# Board_Jam_v3.net
KiCad netlist of a schematic drawn in EAGLE
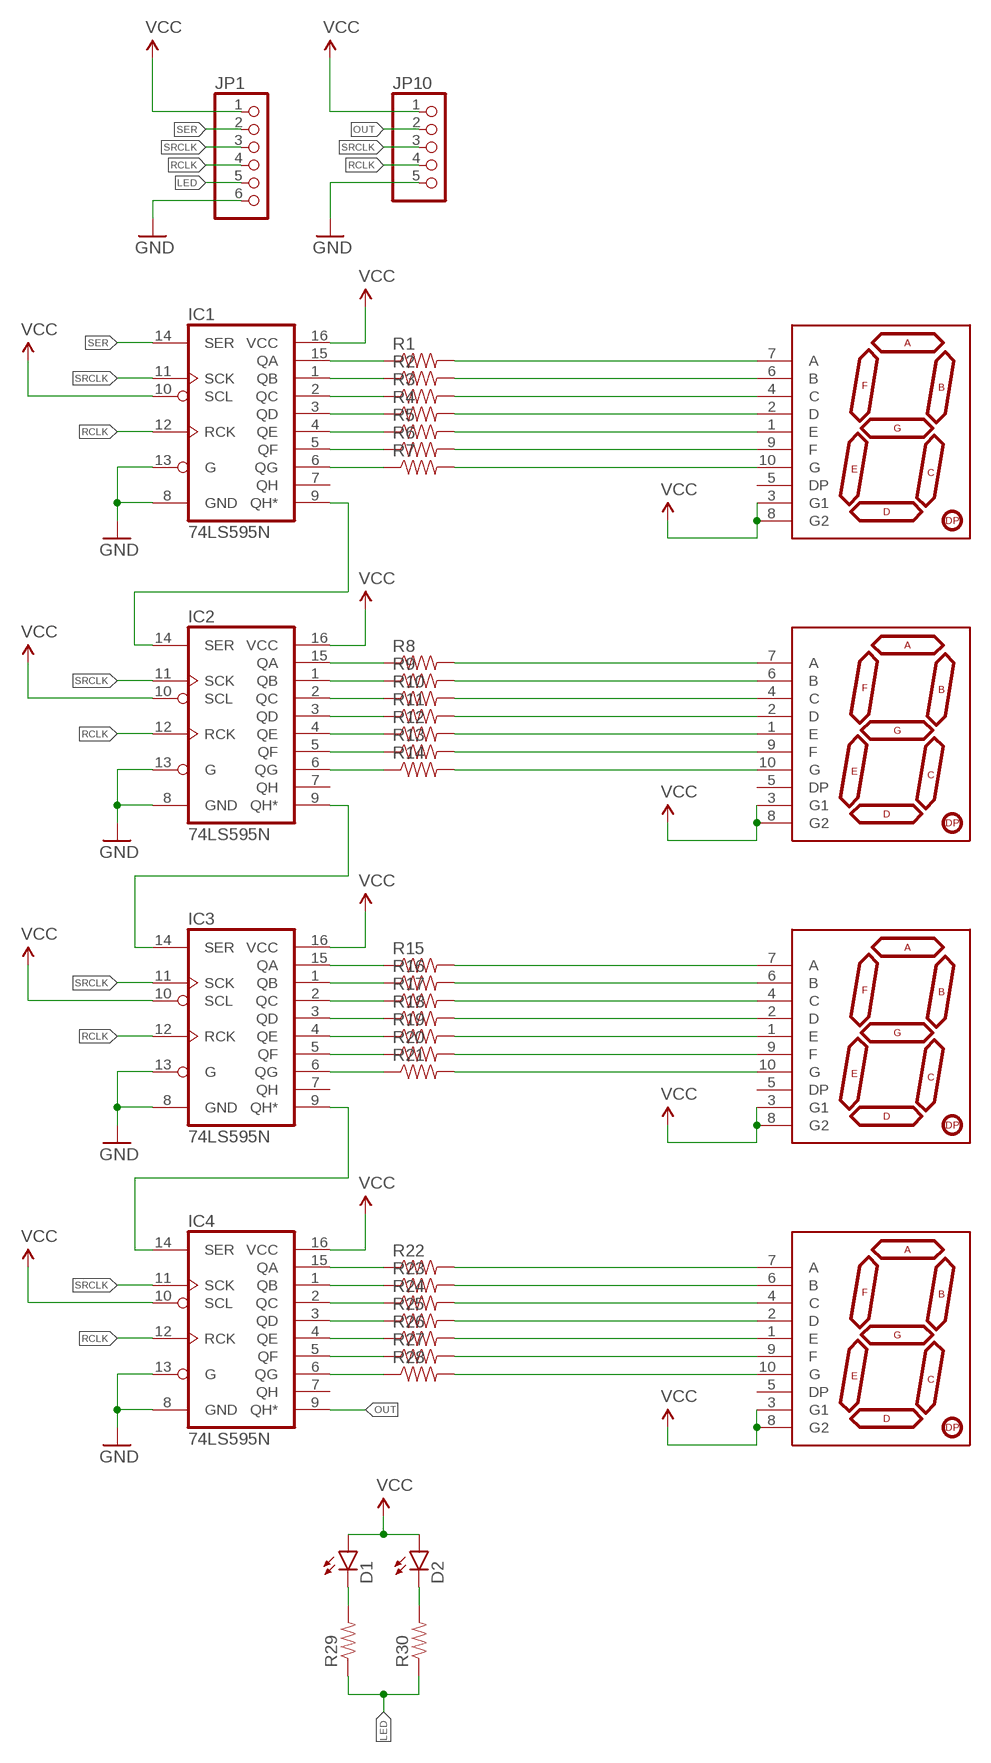
[diagram p0: schematic, sheet 1]

(export (version "E")
  (design (tool "Eeschema 10.0.6"))
  (components
    (comp (ref "D1")
      (value "LED3MM")
      (footprint "eagle-import:LED3MM")
      (libsource (lib "eagle-import") (part "LED3MM"))
    )
    (comp (ref "D2")
      (value "LED3MM")
      (footprint "eagle-import:LED3MM")
      (libsource (lib "eagle-import") (part "LED3MM"))
    )
    (comp (ref "IC1")
      (value "74LS595N")
      (footprint "eagle-import:DIL16")
      (libsource (lib "eagle-import") (part "74595NLS"))
    )
    (comp (ref "IC2")
      (value "74LS595N")
      (footprint "eagle-import:DIL16")
      (libsource (lib "eagle-import") (part "74595NLS"))
    )
    (comp (ref "IC3")
      (value "74LS595N")
      (footprint "eagle-import:DIL16")
      (libsource (lib "eagle-import") (part "74595NLS"))
    )
    (comp (ref "IC4")
      (value "74LS595N")
      (footprint "eagle-import:DIL16")
      (libsource (lib "eagle-import") (part "74595NLS"))
    )
    (comp (ref "JP1")
      (value "PINHD-1X6")
      (footprint "eagle-import:1X06")
      (libsource (lib "eagle-import") (part "PINHD-1X6"))
    )
    (comp (ref "JP10")
      (value "PINHD-1X5")
      (footprint "eagle-import:1X05")
      (libsource (lib "eagle-import") (part "PINHD-1X5"))
    )
    (comp (ref "R1")
      (value "RESISTORPTH-1/4W")
      (footprint "eagle-import:AXIAL-0.4")
      (libsource (lib "eagle-import") (part "RESISTORPTH-1/4W"))
    )
    (comp (ref "R2")
      (value "RESISTORPTH-1/4W")
      (footprint "eagle-import:AXIAL-0.4")
      (libsource (lib "eagle-import") (part "RESISTORPTH-1/4W"))
    )
    (comp (ref "R3")
      (value "RESISTORPTH-1/4W")
      (footprint "eagle-import:AXIAL-0.4")
      (libsource (lib "eagle-import") (part "RESISTORPTH-1/4W"))
    )
    (comp (ref "R4")
      (value "RESISTORPTH-1/4W")
      (footprint "eagle-import:AXIAL-0.4")
      (libsource (lib "eagle-import") (part "RESISTORPTH-1/4W"))
    )
    (comp (ref "R5")
      (value "RESISTORPTH-1/4W")
      (footprint "eagle-import:AXIAL-0.4")
      (libsource (lib "eagle-import") (part "RESISTORPTH-1/4W"))
    )
    (comp (ref "R6")
      (value "RESISTORPTH-1/4W")
      (footprint "eagle-import:AXIAL-0.4")
      (libsource (lib "eagle-import") (part "RESISTORPTH-1/4W"))
    )
    (comp (ref "R7")
      (value "RESISTORPTH-1/4W")
      (footprint "eagle-import:AXIAL-0.4")
      (libsource (lib "eagle-import") (part "RESISTORPTH-1/4W"))
    )
    (comp (ref "R8")
      (value "RESISTORPTH-1/4W")
      (footprint "eagle-import:AXIAL-0.4")
      (libsource (lib "eagle-import") (part "RESISTORPTH-1/4W"))
    )
    (comp (ref "R9")
      (value "RESISTORPTH-1/4W")
      (footprint "eagle-import:AXIAL-0.4")
      (libsource (lib "eagle-import") (part "RESISTORPTH-1/4W"))
    )
    (comp (ref "R10")
      (value "RESISTORPTH-1/4W")
      (footprint "eagle-import:AXIAL-0.4")
      (libsource (lib "eagle-import") (part "RESISTORPTH-1/4W"))
    )
    (comp (ref "R11")
      (value "RESISTORPTH-1/4W")
      (footprint "eagle-import:AXIAL-0.4")
      (libsource (lib "eagle-import") (part "RESISTORPTH-1/4W"))
    )
    (comp (ref "R12")
      (value "RESISTORPTH-1/4W")
      (footprint "eagle-import:AXIAL-0.4")
      (libsource (lib "eagle-import") (part "RESISTORPTH-1/4W"))
    )
    (comp (ref "R13")
      (value "RESISTORPTH-1/4W")
      (footprint "eagle-import:AXIAL-0.4")
      (libsource (lib "eagle-import") (part "RESISTORPTH-1/4W"))
    )
    (comp (ref "R14")
      (value "RESISTORPTH-1/4W")
      (footprint "eagle-import:AXIAL-0.4")
      (libsource (lib "eagle-import") (part "RESISTORPTH-1/4W"))
    )
    (comp (ref "R15")
      (value "RESISTORPTH-1/4W")
      (footprint "eagle-import:AXIAL-0.4")
      (libsource (lib "eagle-import") (part "RESISTORPTH-1/4W"))
    )
    (comp (ref "R16")
      (value "RESISTORPTH-1/4W")
      (footprint "eagle-import:AXIAL-0.4")
      (libsource (lib "eagle-import") (part "RESISTORPTH-1/4W"))
    )
    (comp (ref "R17")
      (value "RESISTORPTH-1/4W")
      (footprint "eagle-import:AXIAL-0.4")
      (libsource (lib "eagle-import") (part "RESISTORPTH-1/4W"))
    )
    (comp (ref "R18")
      (value "RESISTORPTH-1/4W")
      (footprint "eagle-import:AXIAL-0.4")
      (libsource (lib "eagle-import") (part "RESISTORPTH-1/4W"))
    )
    (comp (ref "R19")
      (value "RESISTORPTH-1/4W")
      (footprint "eagle-import:AXIAL-0.4")
      (libsource (lib "eagle-import") (part "RESISTORPTH-1/4W"))
    )
    (comp (ref "R20")
      (value "RESISTORPTH-1/4W")
      (footprint "eagle-import:AXIAL-0.4")
      (libsource (lib "eagle-import") (part "RESISTORPTH-1/4W"))
    )
    (comp (ref "R21")
      (value "RESISTORPTH-1/4W")
      (footprint "eagle-import:AXIAL-0.4")
      (libsource (lib "eagle-import") (part "RESISTORPTH-1/4W"))
    )
    (comp (ref "R22")
      (value "RESISTORPTH-1/4W")
      (footprint "eagle-import:AXIAL-0.4")
      (libsource (lib "eagle-import") (part "RESISTORPTH-1/4W"))
    )
    (comp (ref "R23")
      (value "RESISTORPTH-1/4W")
      (footprint "eagle-import:AXIAL-0.4")
      (libsource (lib "eagle-import") (part "RESISTORPTH-1/4W"))
    )
    (comp (ref "R24")
      (value "RESISTORPTH-1/4W")
      (footprint "eagle-import:AXIAL-0.4")
      (libsource (lib "eagle-import") (part "RESISTORPTH-1/4W"))
    )
    (comp (ref "R25")
      (value "RESISTORPTH-1/4W")
      (footprint "eagle-import:AXIAL-0.4")
      (libsource (lib "eagle-import") (part "RESISTORPTH-1/4W"))
    )
    (comp (ref "R26")
      (value "RESISTORPTH-1/4W")
      (footprint "eagle-import:AXIAL-0.4")
      (libsource (lib "eagle-import") (part "RESISTORPTH-1/4W"))
    )
    (comp (ref "R27")
      (value "RESISTORPTH-1/4W")
      (footprint "eagle-import:AXIAL-0.4")
      (libsource (lib "eagle-import") (part "RESISTORPTH-1/4W"))
    )
    (comp (ref "R28")
      (value "RESISTORPTH-1/4W")
      (footprint "eagle-import:AXIAL-0.4")
      (libsource (lib "eagle-import") (part "RESISTORPTH-1/4W"))
    )
    (comp (ref "R29")
      (value "RESISTORPTH-1/4W")
      (footprint "eagle-import:AXIAL-0.4")
      (libsource (lib "eagle-import") (part "RESISTORPTH-1/4W"))
    )
    (comp (ref "R30")
      (value "RESISTORPTH-1/4W")
      (footprint "eagle-import:AXIAL-0.4")
      (libsource (lib "eagle-import") (part "RESISTORPTH-1/4W"))
    )
    (comp (ref "U$1")
      (value "7-SEGMENT-DISPLAY-1\"-REDEZ")
      (footprint "eagle-import:7-SEGMENT-1_PTH-EZ")
      (libsource (lib "eagle-import") (part "7-SEGMENT-DISPLAY-1{dblquote}-REDEZ"))
    )
    (comp (ref "U$2")
      (value "7-SEGMENT-DISPLAY-1\"-REDEZ")
      (footprint "eagle-import:7-SEGMENT-1_PTH-EZ")
      (libsource (lib "eagle-import") (part "7-SEGMENT-DISPLAY-1{dblquote}-REDEZ"))
    )
    (comp (ref "U$3")
      (value "7-SEGMENT-DISPLAY-1\"-REDEZ")
      (footprint "eagle-import:7-SEGMENT-1_PTH-EZ")
      (libsource (lib "eagle-import") (part "7-SEGMENT-DISPLAY-1{dblquote}-REDEZ"))
    )
    (comp (ref "U$4")
      (value "7-SEGMENT-DISPLAY-1\"-REDEZ")
      (footprint "eagle-import:7-SEGMENT-1_PTH-EZ")
      (libsource (lib "eagle-import") (part "7-SEGMENT-DISPLAY-1{dblquote}-REDEZ"))
    )
  )
  (nets
    (net (code "1") (name "GND") (class "Default")
      (node (ref "IC1") (pin "13") (pinfunction "G_13") (pintype "input"))
      (node (ref "IC1") (pin "8") (pinfunction "GND_8") (pintype "power_in"))
      (node (ref "IC2") (pin "13") (pinfunction "G_13") (pintype "input"))
      (node (ref "IC2") (pin "8") (pinfunction "GND_8") (pintype "power_in"))
      (node (ref "IC3") (pin "13") (pinfunction "G_13") (pintype "input"))
      (node (ref "IC3") (pin "8") (pinfunction "GND_8") (pintype "power_in"))
      (node (ref "IC4") (pin "13") (pinfunction "G_13") (pintype "input"))
      (node (ref "IC4") (pin "8") (pinfunction "GND_8") (pintype "power_in"))
      (node (ref "JP1") (pin "6") (pinfunction "6_6") (pintype "passive"))
      (node (ref "JP10") (pin "5") (pinfunction "5_5") (pintype "passive"))
    )
    (net (code "2") (name "LED") (class "Default")
      (node (ref "JP1") (pin "5") (pinfunction "5_5") (pintype "passive"))
      (node (ref "R29") (pin "P$1") (pinfunction "1_P$1") (pintype "passive"))
      (node (ref "R30") (pin "P$1") (pinfunction "1_P$1") (pintype "passive"))
    )
    (net (code "3") (name "Net-(D1-C)") (class "Default")
      (node (ref "D1") (pin "K") (pinfunction "C_K") (pintype "passive"))
      (node (ref "R29") (pin "P$2") (pinfunction "2_P$2") (pintype "passive"))
    )
    (net (code "4") (name "Net-(D2-C)") (class "Default")
      (node (ref "D2") (pin "K") (pinfunction "C_K") (pintype "passive"))
      (node (ref "R30") (pin "P$2") (pinfunction "2_P$2") (pintype "passive"))
    )
    (net (code "5") (name "Net-(IC1-QA)") (class "Default")
      (node (ref "IC1") (pin "15") (pinfunction "QA_15") (pintype "tri_state"))
      (node (ref "R1") (pin "P$1") (pinfunction "1_P$1") (pintype "passive"))
    )
    (net (code "6") (name "Net-(IC1-QB)") (class "Default")
      (node (ref "IC1") (pin "1") (pinfunction "QB_1") (pintype "tri_state"))
      (node (ref "R2") (pin "P$1") (pinfunction "1_P$1") (pintype "passive"))
    )
    (net (code "7") (name "Net-(IC1-QC)") (class "Default")
      (node (ref "IC1") (pin "2") (pinfunction "QC_2") (pintype "tri_state"))
      (node (ref "R3") (pin "P$1") (pinfunction "1_P$1") (pintype "passive"))
    )
    (net (code "8") (name "Net-(IC1-QD)") (class "Default")
      (node (ref "IC1") (pin "3") (pinfunction "QD_3") (pintype "tri_state"))
      (node (ref "R4") (pin "P$1") (pinfunction "1_P$1") (pintype "passive"))
    )
    (net (code "9") (name "Net-(IC1-QE)") (class "Default")
      (node (ref "IC1") (pin "4") (pinfunction "QE_4") (pintype "tri_state"))
      (node (ref "R5") (pin "P$1") (pinfunction "1_P$1") (pintype "passive"))
    )
    (net (code "10") (name "Net-(IC1-QF)") (class "Default")
      (node (ref "IC1") (pin "5") (pinfunction "QF_5") (pintype "tri_state"))
      (node (ref "R6") (pin "P$1") (pinfunction "1_P$1") (pintype "passive"))
    )
    (net (code "11") (name "Net-(IC1-QG)") (class "Default")
      (node (ref "IC1") (pin "6") (pinfunction "QG_6") (pintype "tri_state"))
      (node (ref "R7") (pin "P$1") (pinfunction "1_P$1") (pintype "passive"))
    )
    (net (code "12") (name "Net-(IC1-QH*)") (class "Default")
      (node (ref "IC1") (pin "9") (pinfunction "QH*_9") (pintype "tri_state"))
      (node (ref "IC2") (pin "14") (pinfunction "SER_14") (pintype "input"))
    )
    (net (code "13") (name "Net-(IC2-QA)") (class "Default")
      (node (ref "IC2") (pin "15") (pinfunction "QA_15") (pintype "tri_state"))
      (node (ref "R8") (pin "P$1") (pinfunction "1_P$1") (pintype "passive"))
    )
    (net (code "14") (name "Net-(IC2-QB)") (class "Default")
      (node (ref "IC2") (pin "1") (pinfunction "QB_1") (pintype "tri_state"))
      (node (ref "R9") (pin "P$1") (pinfunction "1_P$1") (pintype "passive"))
    )
    (net (code "15") (name "Net-(IC2-QC)") (class "Default")
      (node (ref "IC2") (pin "2") (pinfunction "QC_2") (pintype "tri_state"))
      (node (ref "R10") (pin "P$1") (pinfunction "1_P$1") (pintype "passive"))
    )
    (net (code "16") (name "Net-(IC2-QD)") (class "Default")
      (node (ref "IC2") (pin "3") (pinfunction "QD_3") (pintype "tri_state"))
      (node (ref "R11") (pin "P$1") (pinfunction "1_P$1") (pintype "passive"))
    )
    (net (code "17") (name "Net-(IC2-QE)") (class "Default")
      (node (ref "IC2") (pin "4") (pinfunction "QE_4") (pintype "tri_state"))
      (node (ref "R12") (pin "P$1") (pinfunction "1_P$1") (pintype "passive"))
    )
    (net (code "18") (name "Net-(IC2-QF)") (class "Default")
      (node (ref "IC2") (pin "5") (pinfunction "QF_5") (pintype "tri_state"))
      (node (ref "R13") (pin "P$1") (pinfunction "1_P$1") (pintype "passive"))
    )
    (net (code "19") (name "Net-(IC2-QG)") (class "Default")
      (node (ref "IC2") (pin "6") (pinfunction "QG_6") (pintype "tri_state"))
      (node (ref "R14") (pin "P$1") (pinfunction "1_P$1") (pintype "passive"))
    )
    (net (code "20") (name "Net-(IC2-QH*)") (class "Default")
      (node (ref "IC2") (pin "9") (pinfunction "QH*_9") (pintype "tri_state"))
      (node (ref "IC3") (pin "14") (pinfunction "SER_14") (pintype "input"))
    )
    (net (code "21") (name "Net-(IC3-QA)") (class "Default")
      (node (ref "IC3") (pin "15") (pinfunction "QA_15") (pintype "tri_state"))
      (node (ref "R15") (pin "P$1") (pinfunction "1_P$1") (pintype "passive"))
    )
    (net (code "22") (name "Net-(IC3-QB)") (class "Default")
      (node (ref "IC3") (pin "1") (pinfunction "QB_1") (pintype "tri_state"))
      (node (ref "R16") (pin "P$1") (pinfunction "1_P$1") (pintype "passive"))
    )
    (net (code "23") (name "Net-(IC3-QC)") (class "Default")
      (node (ref "IC3") (pin "2") (pinfunction "QC_2") (pintype "tri_state"))
      (node (ref "R17") (pin "P$1") (pinfunction "1_P$1") (pintype "passive"))
    )
    (net (code "24") (name "Net-(IC3-QD)") (class "Default")
      (node (ref "IC3") (pin "3") (pinfunction "QD_3") (pintype "tri_state"))
      (node (ref "R18") (pin "P$1") (pinfunction "1_P$1") (pintype "passive"))
    )
    (net (code "25") (name "Net-(IC3-QE)") (class "Default")
      (node (ref "IC3") (pin "4") (pinfunction "QE_4") (pintype "tri_state"))
      (node (ref "R19") (pin "P$1") (pinfunction "1_P$1") (pintype "passive"))
    )
    (net (code "26") (name "Net-(IC3-QF)") (class "Default")
      (node (ref "IC3") (pin "5") (pinfunction "QF_5") (pintype "tri_state"))
      (node (ref "R20") (pin "P$1") (pinfunction "1_P$1") (pintype "passive"))
    )
    (net (code "27") (name "Net-(IC3-QG)") (class "Default")
      (node (ref "IC3") (pin "6") (pinfunction "QG_6") (pintype "tri_state"))
      (node (ref "R21") (pin "P$1") (pinfunction "1_P$1") (pintype "passive"))
    )
    (net (code "28") (name "Net-(IC3-QH*)") (class "Default")
      (node (ref "IC3") (pin "9") (pinfunction "QH*_9") (pintype "tri_state"))
      (node (ref "IC4") (pin "14") (pinfunction "SER_14") (pintype "input"))
    )
    (net (code "29") (name "Net-(IC4-QA)") (class "Default")
      (node (ref "IC4") (pin "15") (pinfunction "QA_15") (pintype "tri_state"))
      (node (ref "R22") (pin "P$1") (pinfunction "1_P$1") (pintype "passive"))
    )
    (net (code "30") (name "Net-(IC4-QB)") (class "Default")
      (node (ref "IC4") (pin "1") (pinfunction "QB_1") (pintype "tri_state"))
      (node (ref "R23") (pin "P$1") (pinfunction "1_P$1") (pintype "passive"))
    )
    (net (code "31") (name "Net-(IC4-QC)") (class "Default")
      (node (ref "IC4") (pin "2") (pinfunction "QC_2") (pintype "tri_state"))
      (node (ref "R24") (pin "P$1") (pinfunction "1_P$1") (pintype "passive"))
    )
    (net (code "32") (name "Net-(IC4-QD)") (class "Default")
      (node (ref "IC4") (pin "3") (pinfunction "QD_3") (pintype "tri_state"))
      (node (ref "R25") (pin "P$1") (pinfunction "1_P$1") (pintype "passive"))
    )
    (net (code "33") (name "Net-(IC4-QE)") (class "Default")
      (node (ref "IC4") (pin "4") (pinfunction "QE_4") (pintype "tri_state"))
      (node (ref "R26") (pin "P$1") (pinfunction "1_P$1") (pintype "passive"))
    )
    (net (code "34") (name "Net-(IC4-QF)") (class "Default")
      (node (ref "IC4") (pin "5") (pinfunction "QF_5") (pintype "tri_state"))
      (node (ref "R27") (pin "P$1") (pinfunction "1_P$1") (pintype "passive"))
    )
    (net (code "35") (name "Net-(IC4-QG)") (class "Default")
      (node (ref "IC4") (pin "6") (pinfunction "QG_6") (pintype "tri_state"))
      (node (ref "R28") (pin "P$1") (pinfunction "1_P$1") (pintype "passive"))
    )
    (net (code "36") (name "Net-(R1-2)") (class "Default")
      (node (ref "R1") (pin "P$2") (pinfunction "2_P$2") (pintype "passive"))
      (node (ref "U$1") (pin "7") (pinfunction "A_7") (pintype "bidirectional"))
    )
    (net (code "37") (name "Net-(R2-2)") (class "Default")
      (node (ref "R2") (pin "P$2") (pinfunction "2_P$2") (pintype "passive"))
      (node (ref "U$1") (pin "6") (pinfunction "B_6") (pintype "bidirectional"))
    )
    (net (code "38") (name "Net-(R3-2)") (class "Default")
      (node (ref "R3") (pin "P$2") (pinfunction "2_P$2") (pintype "passive"))
      (node (ref "U$1") (pin "4") (pinfunction "C_4") (pintype "bidirectional"))
    )
    (net (code "39") (name "Net-(R4-2)") (class "Default")
      (node (ref "R4") (pin "P$2") (pinfunction "2_P$2") (pintype "passive"))
      (node (ref "U$1") (pin "2") (pinfunction "D_2") (pintype "bidirectional"))
    )
    (net (code "40") (name "Net-(R5-2)") (class "Default")
      (node (ref "R5") (pin "P$2") (pinfunction "2_P$2") (pintype "passive"))
      (node (ref "U$1") (pin "1") (pinfunction "E_1") (pintype "bidirectional"))
    )
    (net (code "41") (name "Net-(R6-2)") (class "Default")
      (node (ref "R6") (pin "P$2") (pinfunction "2_P$2") (pintype "passive"))
      (node (ref "U$1") (pin "9") (pinfunction "F_9") (pintype "bidirectional"))
    )
    (net (code "42") (name "Net-(R7-2)") (class "Default")
      (node (ref "R7") (pin "P$2") (pinfunction "2_P$2") (pintype "passive"))
      (node (ref "U$1") (pin "10") (pinfunction "G_10") (pintype "bidirectional"))
    )
    (net (code "43") (name "Net-(R8-2)") (class "Default")
      (node (ref "R8") (pin "P$2") (pinfunction "2_P$2") (pintype "passive"))
      (node (ref "U$2") (pin "7") (pinfunction "A_7") (pintype "bidirectional"))
    )
    (net (code "44") (name "Net-(R9-2)") (class "Default")
      (node (ref "R9") (pin "P$2") (pinfunction "2_P$2") (pintype "passive"))
      (node (ref "U$2") (pin "6") (pinfunction "B_6") (pintype "bidirectional"))
    )
    (net (code "45") (name "Net-(R10-2)") (class "Default")
      (node (ref "R10") (pin "P$2") (pinfunction "2_P$2") (pintype "passive"))
      (node (ref "U$2") (pin "4") (pinfunction "C_4") (pintype "bidirectional"))
    )
    (net (code "46") (name "Net-(R11-2)") (class "Default")
      (node (ref "R11") (pin "P$2") (pinfunction "2_P$2") (pintype "passive"))
      (node (ref "U$2") (pin "2") (pinfunction "D_2") (pintype "bidirectional"))
    )
    (net (code "47") (name "Net-(R12-2)") (class "Default")
      (node (ref "R12") (pin "P$2") (pinfunction "2_P$2") (pintype "passive"))
      (node (ref "U$2") (pin "1") (pinfunction "E_1") (pintype "bidirectional"))
    )
    (net (code "48") (name "Net-(R13-2)") (class "Default")
      (node (ref "R13") (pin "P$2") (pinfunction "2_P$2") (pintype "passive"))
      (node (ref "U$2") (pin "9") (pinfunction "F_9") (pintype "bidirectional"))
    )
    (net (code "49") (name "Net-(R14-2)") (class "Default")
      (node (ref "R14") (pin "P$2") (pinfunction "2_P$2") (pintype "passive"))
      (node (ref "U$2") (pin "10") (pinfunction "G_10") (pintype "bidirectional"))
    )
    (net (code "50") (name "Net-(R15-2)") (class "Default")
      (node (ref "R15") (pin "P$2") (pinfunction "2_P$2") (pintype "passive"))
      (node (ref "U$3") (pin "7") (pinfunction "A_7") (pintype "bidirectional"))
    )
    (net (code "51") (name "Net-(R16-2)") (class "Default")
      (node (ref "R16") (pin "P$2") (pinfunction "2_P$2") (pintype "passive"))
      (node (ref "U$3") (pin "6") (pinfunction "B_6") (pintype "bidirectional"))
    )
    (net (code "52") (name "Net-(R17-2)") (class "Default")
      (node (ref "R17") (pin "P$2") (pinfunction "2_P$2") (pintype "passive"))
      (node (ref "U$3") (pin "4") (pinfunction "C_4") (pintype "bidirectional"))
    )
    (net (code "53") (name "Net-(R18-2)") (class "Default")
      (node (ref "R18") (pin "P$2") (pinfunction "2_P$2") (pintype "passive"))
      (node (ref "U$3") (pin "2") (pinfunction "D_2") (pintype "bidirectional"))
    )
    (net (code "54") (name "Net-(R19-2)") (class "Default")
      (node (ref "R19") (pin "P$2") (pinfunction "2_P$2") (pintype "passive"))
      (node (ref "U$3") (pin "1") (pinfunction "E_1") (pintype "bidirectional"))
    )
    (net (code "55") (name "Net-(R20-2)") (class "Default")
      (node (ref "R20") (pin "P$2") (pinfunction "2_P$2") (pintype "passive"))
      (node (ref "U$3") (pin "9") (pinfunction "F_9") (pintype "bidirectional"))
    )
    (net (code "56") (name "Net-(R21-2)") (class "Default")
      (node (ref "R21") (pin "P$2") (pinfunction "2_P$2") (pintype "passive"))
      (node (ref "U$3") (pin "10") (pinfunction "G_10") (pintype "bidirectional"))
    )
    (net (code "57") (name "Net-(R22-2)") (class "Default")
      (node (ref "R22") (pin "P$2") (pinfunction "2_P$2") (pintype "passive"))
      (node (ref "U$4") (pin "7") (pinfunction "A_7") (pintype "bidirectional"))
    )
    (net (code "58") (name "Net-(R23-2)") (class "Default")
      (node (ref "R23") (pin "P$2") (pinfunction "2_P$2") (pintype "passive"))
      (node (ref "U$4") (pin "6") (pinfunction "B_6") (pintype "bidirectional"))
    )
    (net (code "59") (name "Net-(R24-2)") (class "Default")
      (node (ref "R24") (pin "P$2") (pinfunction "2_P$2") (pintype "passive"))
      (node (ref "U$4") (pin "4") (pinfunction "C_4") (pintype "bidirectional"))
    )
    (net (code "60") (name "Net-(R25-2)") (class "Default")
      (node (ref "R25") (pin "P$2") (pinfunction "2_P$2") (pintype "passive"))
      (node (ref "U$4") (pin "2") (pinfunction "D_2") (pintype "bidirectional"))
    )
    (net (code "61") (name "Net-(R26-2)") (class "Default")
      (node (ref "R26") (pin "P$2") (pinfunction "2_P$2") (pintype "passive"))
      (node (ref "U$4") (pin "1") (pinfunction "E_1") (pintype "bidirectional"))
    )
    (net (code "62") (name "Net-(R27-2)") (class "Default")
      (node (ref "R27") (pin "P$2") (pinfunction "2_P$2") (pintype "passive"))
      (node (ref "U$4") (pin "9") (pinfunction "F_9") (pintype "bidirectional"))
    )
    (net (code "63") (name "Net-(R28-2)") (class "Default")
      (node (ref "R28") (pin "P$2") (pinfunction "2_P$2") (pintype "passive"))
      (node (ref "U$4") (pin "10") (pinfunction "G_10") (pintype "bidirectional"))
    )
    (net (code "64") (name "OUT") (class "Default")
      (node (ref "IC4") (pin "9") (pinfunction "QH*_9") (pintype "tri_state"))
      (node (ref "JP10") (pin "2") (pinfunction "2_2") (pintype "passive"))
    )
    (net (code "65") (name "RCLK") (class "Default")
      (node (ref "IC1") (pin "12") (pinfunction "RCK_12") (pintype "input"))
      (node (ref "IC2") (pin "12") (pinfunction "RCK_12") (pintype "input"))
      (node (ref "IC3") (pin "12") (pinfunction "RCK_12") (pintype "input"))
      (node (ref "IC4") (pin "12") (pinfunction "RCK_12") (pintype "input"))
      (node (ref "JP1") (pin "4") (pinfunction "4_4") (pintype "passive"))
      (node (ref "JP10") (pin "4") (pinfunction "4_4") (pintype "passive"))
    )
    (net (code "66") (name "SER") (class "Default")
      (node (ref "IC1") (pin "14") (pinfunction "SER_14") (pintype "input"))
      (node (ref "JP1") (pin "2") (pinfunction "2_2") (pintype "passive"))
    )
    (net (code "67") (name "SRCLK") (class "Default")
      (node (ref "IC1") (pin "11") (pinfunction "SCK_11") (pintype "input"))
      (node (ref "IC2") (pin "11") (pinfunction "SCK_11") (pintype "input"))
      (node (ref "IC3") (pin "11") (pinfunction "SCK_11") (pintype "input"))
      (node (ref "IC4") (pin "11") (pinfunction "SCK_11") (pintype "input"))
      (node (ref "JP1") (pin "3") (pinfunction "3_3") (pintype "passive"))
      (node (ref "JP10") (pin "3") (pinfunction "3_3") (pintype "passive"))
    )
    (net (code "68") (name "VCC") (class "Default")
      (node (ref "D1") (pin "A") (pinfunction "A_A") (pintype "passive"))
      (node (ref "D2") (pin "A") (pinfunction "A_A") (pintype "passive"))
      (node (ref "IC1") (pin "10") (pinfunction "SCL_10") (pintype "input"))
      (node (ref "IC1") (pin "16") (pinfunction "VCC_16") (pintype "power_in"))
      (node (ref "IC2") (pin "10") (pinfunction "SCL_10") (pintype "input"))
      (node (ref "IC2") (pin "16") (pinfunction "VCC_16") (pintype "power_in"))
      (node (ref "IC3") (pin "10") (pinfunction "SCL_10") (pintype "input"))
      (node (ref "IC3") (pin "16") (pinfunction "VCC_16") (pintype "power_in"))
      (node (ref "IC4") (pin "10") (pinfunction "SCL_10") (pintype "input"))
      (node (ref "IC4") (pin "16") (pinfunction "VCC_16") (pintype "power_in"))
      (node (ref "JP1") (pin "1") (pinfunction "1_1") (pintype "passive"))
      (node (ref "JP10") (pin "1") (pinfunction "1_1") (pintype "passive"))
      (node (ref "U$1") (pin "3") (pinfunction "G1_3") (pintype "bidirectional"))
      (node (ref "U$1") (pin "8") (pinfunction "G2_8") (pintype "bidirectional"))
      (node (ref "U$2") (pin "3") (pinfunction "G1_3") (pintype "bidirectional"))
      (node (ref "U$2") (pin "8") (pinfunction "G2_8") (pintype "bidirectional"))
      (node (ref "U$3") (pin "3") (pinfunction "G1_3") (pintype "bidirectional"))
      (node (ref "U$3") (pin "8") (pinfunction "G2_8") (pintype "bidirectional"))
      (node (ref "U$4") (pin "3") (pinfunction "G1_3") (pintype "bidirectional"))
      (node (ref "U$4") (pin "8") (pinfunction "G2_8") (pintype "bidirectional"))
    )
    (net (code "69") (name "unconnected-(IC1-QH-Pad7)") (class "Default")
      (node (ref "IC1") (pin "7") (pinfunction "QH_7") (pintype "tri_state"))
    )
    (net (code "70") (name "unconnected-(IC2-QH-Pad7)") (class "Default")
      (node (ref "IC2") (pin "7") (pinfunction "QH_7") (pintype "tri_state"))
    )
    (net (code "71") (name "unconnected-(IC3-QH-Pad7)") (class "Default")
      (node (ref "IC3") (pin "7") (pinfunction "QH_7") (pintype "tri_state"))
    )
    (net (code "72") (name "unconnected-(IC4-QH-Pad7)") (class "Default")
      (node (ref "IC4") (pin "7") (pinfunction "QH_7") (pintype "tri_state"))
    )
    (net (code "73") (name "unconnected-(U$1-DP-Pad5)") (class "Default")
      (node (ref "U$1") (pin "5") (pinfunction "DP_5") (pintype "bidirectional"))
    )
    (net (code "74") (name "unconnected-(U$2-DP-Pad5)") (class "Default")
      (node (ref "U$2") (pin "5") (pinfunction "DP_5") (pintype "bidirectional"))
    )
    (net (code "75") (name "unconnected-(U$3-DP-Pad5)") (class "Default")
      (node (ref "U$3") (pin "5") (pinfunction "DP_5") (pintype "bidirectional"))
    )
    (net (code "76") (name "unconnected-(U$4-DP-Pad5)") (class "Default")
      (node (ref "U$4") (pin "5") (pinfunction "DP_5") (pintype "bidirectional"))
    )
  )
)
